# activeIr.net
KiCad netlist of a schematic drawn in EAGLE
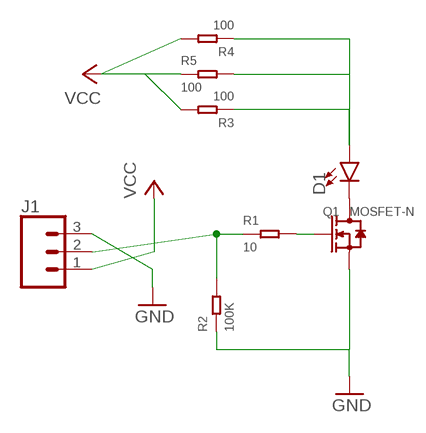
[diagram p0: schematic, sheet 1]

(export (version "E")
  (design (tool "Eeschema 10.0.6"))
  (components
    (comp (ref "D1")
      (value "LED5MM")
      (footprint "eagle-import:LED_5MM")
      (libsource (lib "eagle-import") (part "LED5MM"))
    )
    (comp (ref "J1")
      (value "CONN_03SMD_RA_MALE")
      (footprint "eagle-import:1X03_SMD_RA_MALE")
      (libsource (lib "eagle-import") (part "CONN_03SMD_RA_MALE"))
    )
    (comp (ref "Q1")
      (value "MOSFET-N")
      (footprint "eagle-import:SOT-23")
      (libsource (lib "eagle-import") (part "MOSFET-N"))
    )
    (comp (ref "R1")
      (value "10")
      (footprint "eagle-import:R0603")
      (libsource (lib "eagle-import") (part "RES-0603"))
    )
    (comp (ref "R2")
      (value "100K")
      (footprint "eagle-import:R0603")
      (libsource (lib "eagle-import") (part "RES-0603"))
    )
    (comp (ref "R3")
      (value "100")
      (footprint "eagle-import:R1206")
      (libsource (lib "eagle-import") (part "RES-1206"))
    )
    (comp (ref "R4")
      (value "100")
      (footprint "eagle-import:R1206")
      (libsource (lib "eagle-import") (part "RES-1206"))
    )
    (comp (ref "R5")
      (value "100")
      (footprint "eagle-import:R1206")
      (libsource (lib "eagle-import") (part "RES-1206"))
    )
  )
  (nets
    (net (code "1") (name "GND") (class "Default")
      (node (ref "J1") (pin "3") (pinfunction "3_3") (pintype "passive"))
      (node (ref "Q1") (pin "2") (pinfunction "S_2") (pintype "passive"))
      (node (ref "R2") (pin "1") (pinfunction "1_1") (pintype "passive"))
    )
    (net (code "2") (name "Net-(D1-C)") (class "Default")
      (node (ref "D1") (pin "K") (pinfunction "C_K") (pintype "passive"))
      (node (ref "Q1") (pin "3") (pinfunction "D_3") (pintype "passive"))
    )
    (net (code "3") (name "Net-(D1-PadA)") (class "Default")
      (node (ref "D1") (pin "A") (pinfunction "A_A") (pintype "passive"))
      (node (ref "R3") (pin "1") (pinfunction "1_1") (pintype "passive"))
      (node (ref "R4") (pin "1") (pinfunction "1_1") (pintype "passive"))
      (node (ref "R5") (pin "2") (pinfunction "2_2") (pintype "passive"))
    )
    (net (code "4") (name "Net-(J1-Pad2)") (class "Default")
      (node (ref "J1") (pin "2") (pinfunction "2_2") (pintype "passive"))
      (node (ref "R1") (pin "1") (pinfunction "1_1") (pintype "passive"))
      (node (ref "R2") (pin "2") (pinfunction "2_2") (pintype "passive"))
    )
    (net (code "5") (name "Net-(Q1-G)") (class "Default")
      (node (ref "Q1") (pin "1") (pinfunction "G_1") (pintype "passive"))
      (node (ref "R1") (pin "2") (pinfunction "2_2") (pintype "passive"))
    )
    (net (code "6") (name "VCC") (class "Default")
      (node (ref "J1") (pin "1") (pinfunction "1_1") (pintype "passive"))
      (node (ref "R3") (pin "2") (pinfunction "2_2") (pintype "passive"))
      (node (ref "R4") (pin "2") (pinfunction "2_2") (pintype "passive"))
      (node (ref "R5") (pin "1") (pinfunction "1_1") (pintype "passive"))
    )
  )
)
